# POwer.net
KiCad netlist of a schematic drawn in Altium Designer
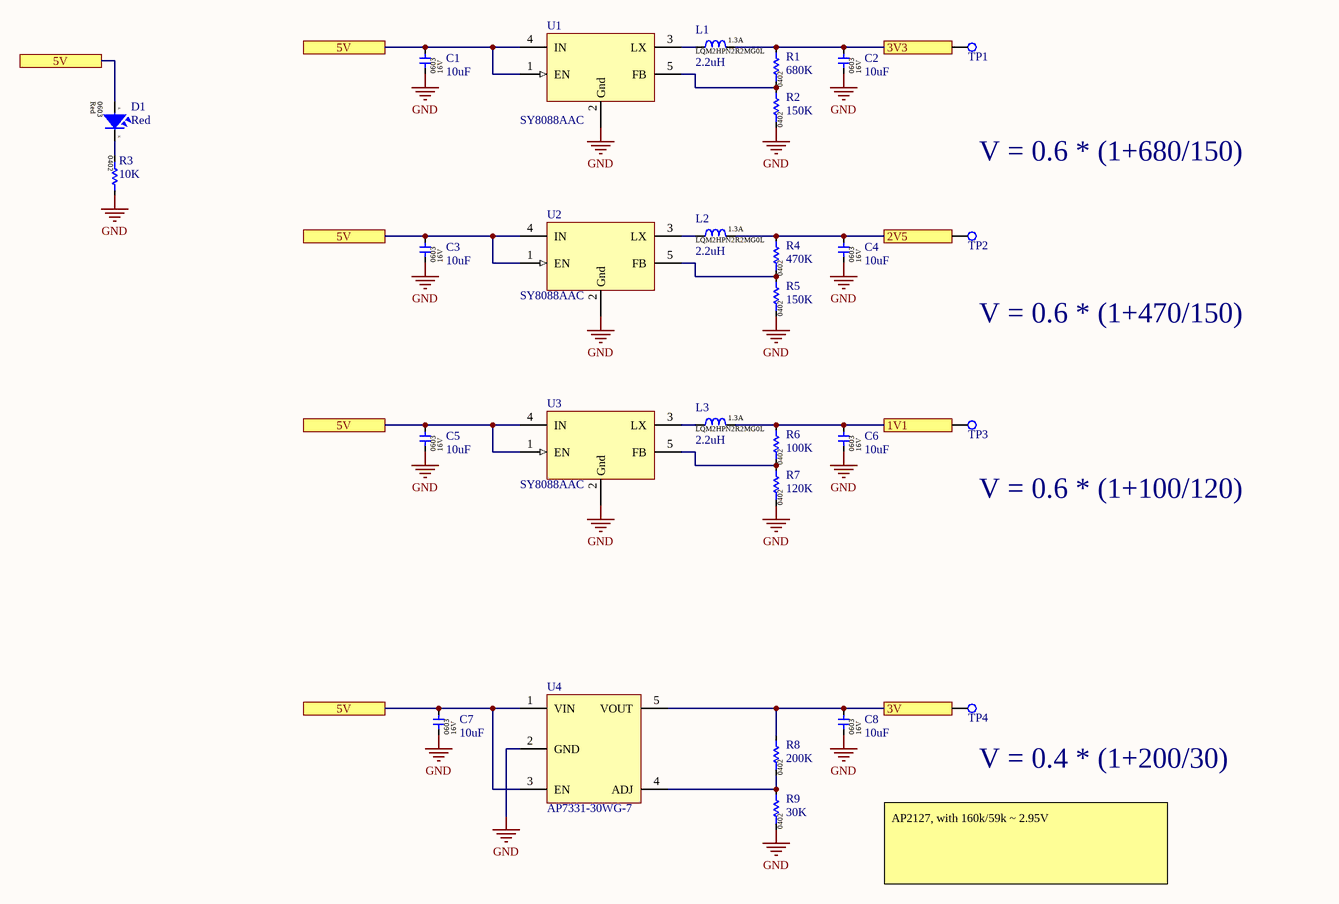
[diagram p0: POwer.SchDoc]

(export (version "E")
  (design (tool "Eeschema 10.0.6"))
  (components
    (comp (ref "C1")
      (value "10uF")
      (footprint "CAP-0603")
      (description "16V 10uF X5R ±20% 0603 Multilayer Ceramic Capacitors MLCC - SMD/SMT ROHS")
      (fields (field (name "MANUFACTURE PART") "0603X106M160CT") (field (name "VOLTAGE") "16V"))
      (libsource (lib "Capacitor Database") (part "Cap-non-polarized"))
    )
    (comp (ref "C2")
      (value "10uF")
      (footprint "CAP-0603")
      (description "16V 10uF X5R ±20% 0603 Multilayer Ceramic Capacitors MLCC - SMD/SMT ROHS")
      (fields (field (name "MANUFACTURE PART") "0603X106M160CT") (field (name "VOLTAGE") "16V"))
      (libsource (lib "Capacitor Database") (part "Cap-non-polarized"))
    )
    (comp (ref "C3")
      (value "10uF")
      (footprint "CAP-0603")
      (description "16V 10uF X5R ±20% 0603 Multilayer Ceramic Capacitors MLCC - SMD/SMT ROHS")
      (fields (field (name "MANUFACTURE PART") "0603X106M160CT") (field (name "VOLTAGE") "16V"))
      (libsource (lib "Capacitor Database") (part "Cap-non-polarized"))
    )
    (comp (ref "C4")
      (value "10uF")
      (footprint "CAP-0603")
      (description "16V 10uF X5R ±20% 0603 Multilayer Ceramic Capacitors MLCC - SMD/SMT ROHS")
      (fields (field (name "MANUFACTURE PART") "0603X106M160CT") (field (name "VOLTAGE") "16V"))
      (libsource (lib "Capacitor Database") (part "Cap-non-polarized"))
    )
    (comp (ref "C5")
      (value "10uF")
      (footprint "CAP-0603")
      (description "16V 10uF X5R ±20% 0603 Multilayer Ceramic Capacitors MLCC - SMD/SMT ROHS")
      (fields (field (name "MANUFACTURE PART") "0603X106M160CT") (field (name "VOLTAGE") "16V"))
      (libsource (lib "Capacitor Database") (part "Cap-non-polarized"))
    )
    (comp (ref "C6")
      (value "10uF")
      (footprint "CAP-0603")
      (description "16V 10uF X5R ±20% 0603 Multilayer Ceramic Capacitors MLCC - SMD/SMT ROHS")
      (fields (field (name "MANUFACTURE PART") "0603X106M160CT") (field (name "VOLTAGE") "16V"))
      (libsource (lib "Capacitor Database") (part "Cap-non-polarized"))
    )
    (comp (ref "C7")
      (value "10uF")
      (footprint "CAP-0603")
      (description "16V 10uF X5R ±20% 0603 Multilayer Ceramic Capacitors MLCC - SMD/SMT ROHS")
      (fields (field (name "MANUFACTURE PART") "0603X106M160CT") (field (name "VOLTAGE") "16V"))
      (libsource (lib "Capacitor Database") (part "Cap-non-polarized"))
    )
    (comp (ref "C8")
      (value "10uF")
      (footprint "CAP-0603")
      (description "16V 10uF X5R ±20% 0603 Multilayer Ceramic Capacitors MLCC - SMD/SMT ROHS")
      (fields (field (name "MANUFACTURE PART") "0603X106M160CT") (field (name "VOLTAGE") "16V"))
      (libsource (lib "Capacitor Database") (part "Cap-non-polarized"))
    )
    (comp (ref "D1")
      (value "Red")
      (footprint "LED-0603 RED")
      (description "Red 617.5~633.5nm 0603 Light Emitting Diodes (LED) RoHS")
      (fields (field (name "MANUFACTURE PART") "19-217/R6C-AL1M2VY/3T"))
      (libsource (lib "Led Database") (part "Led"))
    )
    (comp (ref "L1")
      (value "2.2uH")
      (footprint "IND-1008")
      (description "Inductor 1008, 2.2±20%, 1.3A")
      (fields (field (name "MANUFACTURE PART") "LQM2HPN2R2MG0L"))
      (libsource (lib "Inductor Database") (part "Inductor"))
    )
    (comp (ref "L2")
      (value "2.2uH")
      (footprint "IND-1008")
      (description "Inductor 1008, 2.2±20%, 1.3A")
      (fields (field (name "MANUFACTURE PART") "LQM2HPN2R2MG0L"))
      (libsource (lib "Inductor Database") (part "Inductor"))
    )
    (comp (ref "L3")
      (value "2.2uH")
      (footprint "IND-1008")
      (description "Inductor 1008, 2.2±20%, 1.3A")
      (fields (field (name "MANUFACTURE PART") "LQM2HPN2R2MG0L"))
      (libsource (lib "Inductor Database") (part "Inductor"))
    )
    (comp (ref "R1")
      (value "680K")
      (footprint "RES-0402")
      (description "±1% 1/16W 50V ±100ppm/℃ -55℃~+155℃ 680kΩ 0402 Chip Resistor - Surface Mount ROHS")
      (fields (field (name "MANUFACTURE PART") "WR04X6803FTL"))
      (libsource (lib "Resistor Database") (part "Resistor"))
    )
    (comp (ref "R2")
      (value "150K")
      (footprint "RES-0402")
      (description "150kΩ ±1% 1/16W ±100ppm/℃ 0402 Chip Resistor - Surface Mount RoHS")
      (fields (field (name "MANUFACTURE PART") "WR04X1503FTL"))
      (libsource (lib "Resistor Database") (part "Resistor"))
    )
    (comp (ref "R3")
      (value "10K")
      (footprint "RES-0402")
      (description "10kΩ ±1% 1/16W ±100ppm/℃ 0402 Chip Resistor - Surface Mount RoHS")
      (fields (field (name "MANUFACTURE PART") "WR04X1002FTL"))
      (libsource (lib "Resistor Database") (part "Resistor"))
    )
    (comp (ref "R4")
      (value "470K")
      (footprint "RES-0402")
      (description "±1% 1/16W 50V ±100ppm/℃ -55℃~+155℃ 470kΩ 0402 Chip Resistor - Surface Mount ROHS")
      (fields (field (name "MANUFACTURE PART") "WR04X4703FTL"))
      (libsource (lib "Resistor Database") (part "Resistor"))
    )
    (comp (ref "R5")
      (value "150K")
      (footprint "RES-0402")
      (description "150kΩ ±1% 1/16W ±100ppm/℃ 0402 Chip Resistor - Surface Mount RoHS")
      (fields (field (name "MANUFACTURE PART") "WR04X1503FTL"))
      (libsource (lib "Resistor Database") (part "Resistor"))
    )
    (comp (ref "R6")
      (value "100K")
      (footprint "RES-0402")
      (description "100kΩ ±1% 1/16W ±100ppm/℃ 0402 Chip Resistor - Surface Mount RoHS")
      (fields (field (name "MANUFACTURE PART") "WR04X1003FTL"))
      (libsource (lib "Resistor Database") (part "Resistor"))
    )
    (comp (ref "R7")
      (value "120K")
      (footprint "RES-0402")
      (description "120kΩ ±1% 1/16W ±100ppm/℃ 0402 Chip Resistor - Surface Mount RoHS")
      (fields (field (name "MANUFACTURE PART") "WR04X1203FTL"))
      (libsource (lib "Resistor Database") (part "Resistor"))
    )
    (comp (ref "R8")
      (value "200K")
      (footprint "RES-0402")
      (description "200kΩ ±1% 1/16W ±100ppm/℃ 0402 Chip Resistor - Surface Mount RoHS")
      (fields (field (name "MANUFACTURE PART") "WR04X2003FTL"))
      (libsource (lib "Resistor Database") (part "Resistor"))
    )
    (comp (ref "R9")
      (value "30K")
      (footprint "RES-0402")
      (description "±1% 1/16W ±100ppm/℃ 30kΩ 0402 Chip Resistor - Surface Mount ROHS")
      (fields (field (name "MANUFACTURE PART") "WR04X3002FTL"))
      (libsource (lib "Resistor Database") (part "Resistor"))
    )
    (comp (ref "TP1")
      (value "N/A")
      (footprint "Test point")
      (description "A point used for measure.")
      (libsource (lib "Connectors, Misc") (part "Test point"))
    )
    (comp (ref "TP2")
      (value "N/A")
      (footprint "Test point")
      (description "A point used for measure.")
      (libsource (lib "Connectors, Misc") (part "Test point"))
    )
    (comp (ref "TP3")
      (value "N/A")
      (footprint "Test point")
      (description "A point used for measure.")
      (libsource (lib "Connectors, Misc") (part "Test point"))
    )
    (comp (ref "TP4")
      (value "N/A")
      (footprint "Test point")
      (description "A point used for measure.")
      (libsource (lib "Connectors, Misc") (part "Test point"))
    )
    (comp (ref "U1")
      (value "SY8088AAC")
      (footprint "SOT23-5")
      (description "5.5V 1A SOT-23-5 DC-DC Converters RoHS")
      (libsource (lib "Regulator Database") (part "SY80xx"))
    )
    (comp (ref "U2")
      (value "SY8088AAC")
      (footprint "SOT23-5")
      (description "5.5V 1A SOT-23-5 DC-DC Converters RoHS")
      (libsource (lib "Regulator Database") (part "SY80xx"))
    )
    (comp (ref "U3")
      (value "SY8088AAC")
      (footprint "SOT23-5")
      (description "5.5V 1A SOT-23-5 DC-DC Converters RoHS")
      (libsource (lib "Regulator Database") (part "SY80xx"))
    )
    (comp (ref "U4")
      (value "AP7331-30WG-7")
      (footprint "SOT23-5")
      (description "Fixed 6V 3V 550mV @ 300mA SOT-25 Dropout Regulators(LDO) RoHS")
      (fields (field (name "PART NUMBER") "AP7331-WG-7"))
      (libsource (lib "Regulator Database") (part "AP7331"))
    )
  )
  (nets
    (net (code "1") (name "/1V1") (class "Default")
      (node (ref "C6") (pin "2") (pinfunction "2_2") (pintype "passive"))
      (node (ref "L3") (pin "2") (pinfunction "2_2") (pintype "passive"))
      (node (ref "R6") (pin "2") (pinfunction "2_2") (pintype "passive"))
      (node (ref "TP3") (pin "1") (pinfunction "1_1") (pintype "passive"))
    )
    (net (code "2") (name "/2V5") (class "Default")
      (node (ref "C4") (pin "2") (pinfunction "2_2") (pintype "passive"))
      (node (ref "L2") (pin "2") (pinfunction "2_2") (pintype "passive"))
      (node (ref "R4") (pin "2") (pinfunction "2_2") (pintype "passive"))
      (node (ref "TP2") (pin "1") (pinfunction "1_1") (pintype "passive"))
    )
    (net (code "3") (name "/3V") (class "Default")
      (node (ref "C8") (pin "2") (pinfunction "2_2") (pintype "passive"))
      (node (ref "R8") (pin "2") (pinfunction "2_2") (pintype "passive"))
      (node (ref "TP4") (pin "1") (pinfunction "1_1") (pintype "passive"))
      (node (ref "U4") (pin "5") (pinfunction "VOUT_5") (pintype "passive"))
    )
    (net (code "4") (name "/3V3") (class "Default")
      (node (ref "C2") (pin "2") (pinfunction "2_2") (pintype "passive"))
      (node (ref "L1") (pin "2") (pinfunction "2_2") (pintype "passive"))
      (node (ref "R1") (pin "2") (pinfunction "2_2") (pintype "passive"))
      (node (ref "TP1") (pin "1") (pinfunction "1_1") (pintype "passive"))
    )
    (net (code "5") (name "/5V") (class "Default")
      (node (ref "C1") (pin "2") (pinfunction "2_2") (pintype "passive"))
      (node (ref "C3") (pin "2") (pinfunction "2_2") (pintype "passive"))
      (node (ref "C5") (pin "2") (pinfunction "2_2") (pintype "passive"))
      (node (ref "C7") (pin "2") (pinfunction "2_2") (pintype "passive"))
      (node (ref "D1") (pin "2") (pinfunction "Anode_2") (pintype "passive"))
      (node (ref "U1") (pin "1") (pinfunction "EN_1") (pintype "input"))
      (node (ref "U1") (pin "4") (pinfunction "IN_4") (pintype "power_in"))
      (node (ref "U2") (pin "1") (pinfunction "EN_1") (pintype "input"))
      (node (ref "U2") (pin "4") (pinfunction "IN_4") (pintype "power_in"))
      (node (ref "U3") (pin "1") (pinfunction "EN_1") (pintype "input"))
      (node (ref "U3") (pin "4") (pinfunction "IN_4") (pintype "power_in"))
      (node (ref "U4") (pin "1") (pinfunction "VIN_1") (pintype "passive"))
      (node (ref "U4") (pin "3") (pinfunction "EN_3") (pintype "passive"))
    )
    (net (code "6") (name "GND") (class "Default")
      (node (ref "C1") (pin "1") (pinfunction "1_1") (pintype "passive"))
      (node (ref "C2") (pin "1") (pinfunction "1_1") (pintype "passive"))
      (node (ref "C3") (pin "1") (pinfunction "1_1") (pintype "passive"))
      (node (ref "C4") (pin "1") (pinfunction "1_1") (pintype "passive"))
      (node (ref "C5") (pin "1") (pinfunction "1_1") (pintype "passive"))
      (node (ref "C6") (pin "1") (pinfunction "1_1") (pintype "passive"))
      (node (ref "C7") (pin "1") (pinfunction "1_1") (pintype "passive"))
      (node (ref "C8") (pin "1") (pinfunction "1_1") (pintype "passive"))
      (node (ref "R2") (pin "1") (pinfunction "1_1") (pintype "passive"))
      (node (ref "R3") (pin "2") (pinfunction "2_2") (pintype "passive"))
      (node (ref "R5") (pin "1") (pinfunction "1_1") (pintype "passive"))
      (node (ref "R7") (pin "1") (pinfunction "1_1") (pintype "passive"))
      (node (ref "R9") (pin "1") (pinfunction "1_1") (pintype "passive"))
      (node (ref "U1") (pin "2") (pinfunction "Gnd_2") (pintype "passive"))
      (node (ref "U2") (pin "2") (pinfunction "Gnd_2") (pintype "passive"))
      (node (ref "U3") (pin "2") (pinfunction "Gnd_2") (pintype "passive"))
      (node (ref "U4") (pin "2") (pinfunction "GND_2") (pintype "passive"))
    )
    (net (code "7") (name "Net-(D1-Cathode)") (class "Default")
      (node (ref "D1") (pin "1") (pinfunction "Cathode_1") (pintype "passive"))
      (node (ref "R3") (pin "1") (pinfunction "1_1") (pintype "passive"))
    )
    (net (code "8") (name "Net-(U1-FB)") (class "Default")
      (node (ref "R1") (pin "1") (pinfunction "1_1") (pintype "passive"))
      (node (ref "R2") (pin "2") (pinfunction "2_2") (pintype "passive"))
      (node (ref "U1") (pin "5") (pinfunction "FB_5") (pintype "passive"))
    )
    (net (code "9") (name "Net-(U1-LX)") (class "Default")
      (node (ref "L1") (pin "1") (pinfunction "1_1") (pintype "passive"))
      (node (ref "U1") (pin "3") (pinfunction "LX_3") (pintype "power_in"))
    )
    (net (code "10") (name "Net-(U2-FB)") (class "Default")
      (node (ref "R4") (pin "1") (pinfunction "1_1") (pintype "passive"))
      (node (ref "R5") (pin "2") (pinfunction "2_2") (pintype "passive"))
      (node (ref "U2") (pin "5") (pinfunction "FB_5") (pintype "passive"))
    )
    (net (code "11") (name "Net-(U2-LX)") (class "Default")
      (node (ref "L2") (pin "1") (pinfunction "1_1") (pintype "passive"))
      (node (ref "U2") (pin "3") (pinfunction "LX_3") (pintype "power_in"))
    )
    (net (code "12") (name "Net-(U3-FB)") (class "Default")
      (node (ref "R6") (pin "1") (pinfunction "1_1") (pintype "passive"))
      (node (ref "R7") (pin "2") (pinfunction "2_2") (pintype "passive"))
      (node (ref "U3") (pin "5") (pinfunction "FB_5") (pintype "passive"))
    )
    (net (code "13") (name "Net-(U3-LX)") (class "Default")
      (node (ref "L3") (pin "1") (pinfunction "1_1") (pintype "passive"))
      (node (ref "U3") (pin "3") (pinfunction "LX_3") (pintype "power_in"))
    )
    (net (code "14") (name "Net-(U4-ADJ)") (class "Default")
      (node (ref "R8") (pin "1") (pinfunction "1_1") (pintype "passive"))
      (node (ref "R9") (pin "2") (pinfunction "2_2") (pintype "passive"))
      (node (ref "U4") (pin "4") (pinfunction "ADJ_4") (pintype "passive"))
    )
  )
)
